# Audio_Amplifier.net
KiCad netlist of a schematic drawn in Altium Designer
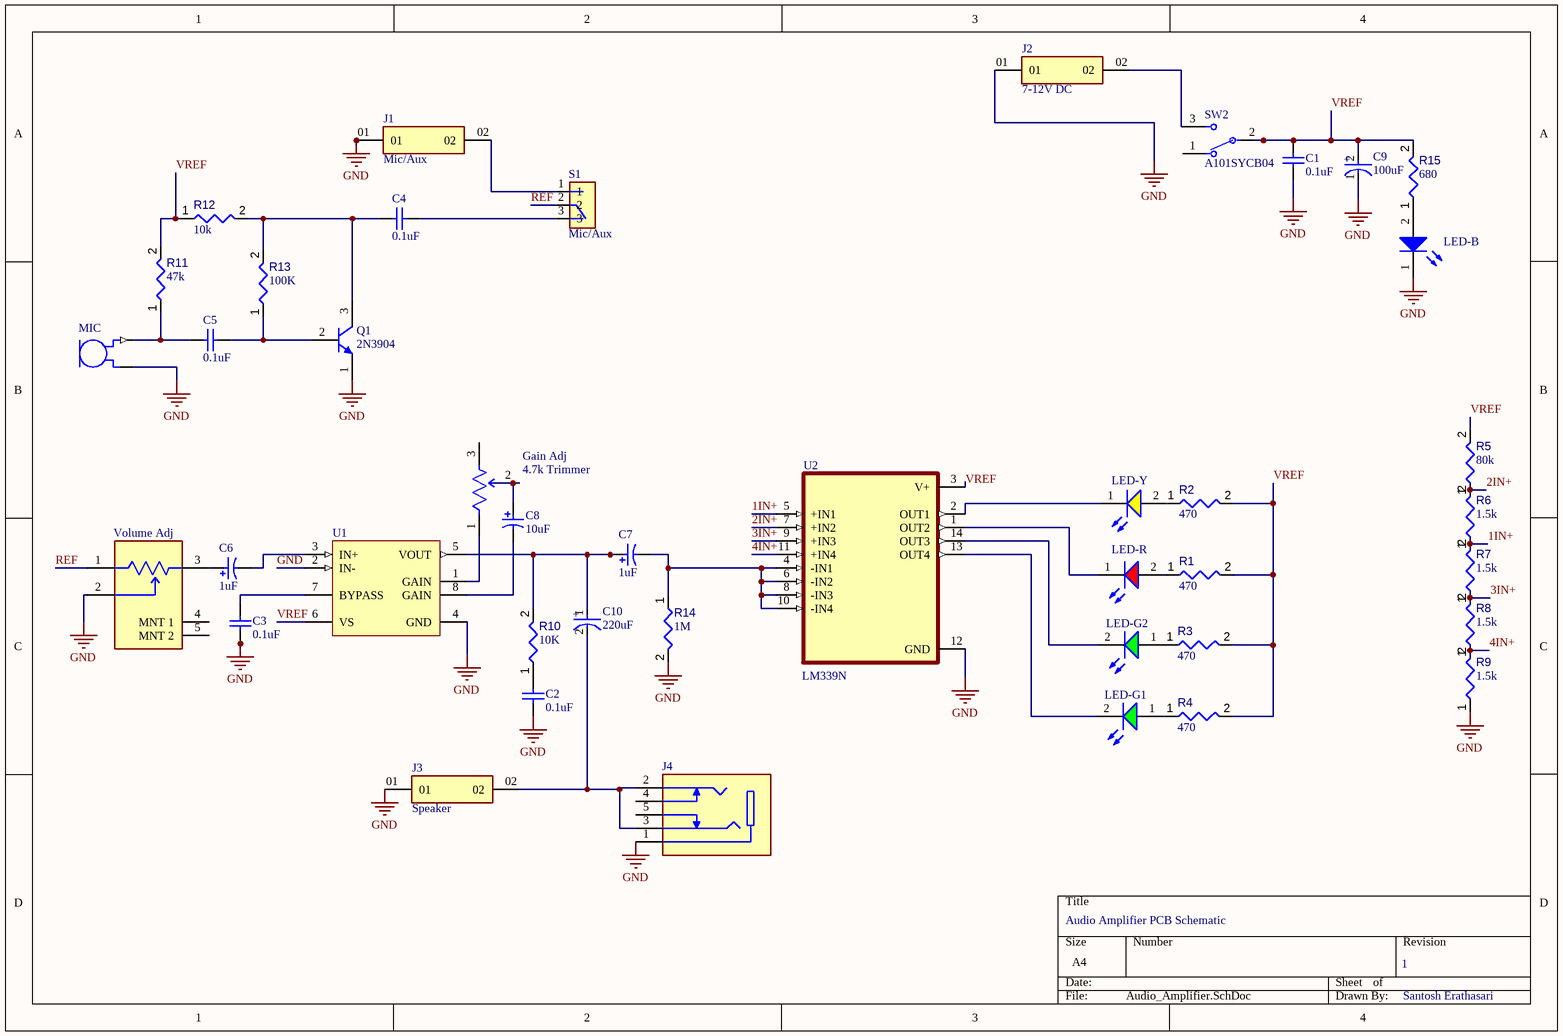
[diagram p0: Audio_Amplifier.SchDoc]

(export (version "E")
  (design (tool "Eeschema 10.0.6"))
  (components
    (comp (ref "C1")
      (value "0.1uF")
      (footprint "CAPR51-254-508X318X736")
      (libsource (lib "Altium Content Vault") (part "CAP-NP-2"))
    )
    (comp (ref "C2")
      (value "0.1uF")
      (footprint "CAPR51-254-508X318X736")
      (libsource (lib "Altium Content Vault") (part "CAP-NP-2"))
    )
    (comp (ref "C3")
      (value "0.1uF")
      (footprint "CAPR51-254-508X318X736")
      (libsource (lib "Altium Content Vault") (part "CAP-NP-2"))
    )
    (comp (ref "C4")
      (value "0.1uF")
      (footprint "CAPR51-254-508X318X736")
      (libsource (lib "Altium Content Vault") (part "CAP-NP-2"))
    )
    (comp (ref "C5")
      (value "0.1uF")
      (footprint "CAPR51-254-508X318X736")
      (libsource (lib "Altium Content Vault") (part "CAP-NP-2"))
    )
    (comp (ref "C6")
      (value "1uF")
      (footprint "CAPPR55-200-1100X500X1200")
      (description "Aluminum Electrolytic Capacitor, 1 uF, +/- 20%, 50 V, -55 to 105 degC, 2-Pin THD, RoHS, Bulk")
      (libsource (lib "Altium Content Vault") (part "CAP-P-2"))
    )
    (comp (ref "C7")
      (value "1uF")
      (footprint "CAPPR55-200-1100X500X1200")
      (description "Aluminum Electrolytic Capacitor, 1 uF, +/- 20%, 50 V, -55 to 105 degC, 2-Pin THD, RoHS, Bulk")
      (libsource (lib "Altium Content Vault") (part "CAP-P-2"))
    )
    (comp (ref "C8")
      (value "10uF")
      (footprint "CAPPR55-200-1100X500X1200")
      (description "Aluminum Electrolytic Capacitor, 10 uF, +/- 20%, 50 V, -40 to 85 degC, 2-Pin THD, RoHS, Bulk")
      (fields (field (name "MANUFACTURER") "Panasonic") (field (name "TOLERANCE") "20%"))
      (libsource (lib "Altium Content Vault") (part "CAP-P-2"))
    )
    (comp (ref "C9")
      (value "100uF")
      (footprint "FP-RAD-TH-D_6_3_0_5-L_11-MFG")
      (description "Aluminum Electrolytic Capacitors (Radial Lead Type) 100uF ±20% 25V")
      (libsource (lib "Altium Content Vault") (part "a00bbbee19879c290e62620ae7e47b1"))
    )
    (comp (ref "C10")
      (value "220uF")
      (footprint "FP-EEU-FC1V221L-MFG")
      (description "CAP ALUM 220UF 20% 35V RADIAL")
      (fields
        (field (name "OCTOPART") "https://octopart.com/eeu-fc1v221l-panasonic-39478519")
        (field (name "MANUFACTURER") "Panasonic Electronic Components")
      )
      (libsource (lib "Altium Content Vault") (part "385ce6c70a3ab0aa1e866f00bd8ed49"))
    )
    (comp (ref "Gain Adj")
      (value "4.7k Trimmer")
      (footprint "FP-3362U-MFG")
      (description "TRIMMER 200K OHM 0.5W PC PIN TOP")
      (fields (field (name "TOLERANCE") "10%"))
      (libsource (lib "Altium Content Vault") (part "2dcfd2547301a7d3209a5e99acfd772"))
    )
    (comp (ref "J1")
      (value "Mic/Aux")
      (footprint "SAMTEC_HTSW-101-08-T-D")
      (fields (field (name "MP") "HTSW-101-08-T-D"))
      (libsource (lib "HTSW-101-08-T-D") (part "HTSW-101-08-T-D"))
    )
    (comp (ref "J2")
      (value "7-12V DC")
      (footprint "SAMTEC_HTSW-101-08-T-D")
      (fields (field (name "MP") "HTSW-101-08-T-D"))
      (libsource (lib "HTSW-101-08-T-D") (part "HTSW-101-08-T-D"))
    )
    (comp (ref "J3")
      (value "Speaker")
      (footprint "SAMTEC_HTSW-101-08-T-D")
      (fields (field (name "MP") "HTSW-101-08-T-D"))
      (libsource (lib "HTSW-101-08-T-D") (part "HTSW-101-08-T-D"))
    )
    (comp (ref "J4")
      (value "SJ1-3525NG")
      (footprint "CUI_SJ1-3525NG")
      (description "3.5 mm Right-Angle Stereo Jack, 5 Pin PCB Mount, Isolated Ground")
      (libsource (lib "Santosh's Playhouse") (part "SJ1-3525NG"))
    )
    (comp (ref "LED-B")
      (value "LED-B")
      (footprint "WL-TMRW_D5.8H11.7")
      (libsource (lib "Altium Content Vault") (part "LED_Blue_2A-1K"))
    )
    (comp (ref "LED-G1")
      (value "151051VS04000")
      (footprint "WL-TMRC_D5.9H8.7")
      (libsource (lib "Altium Content Vault") (part "LED_Green_1A-2K"))
    )
    (comp (ref "LED-G2")
      (value "151051VS04000")
      (footprint "WL-TMRC_D5.9H8.7")
      (libsource (lib "Altium Content Vault") (part "LED_Green_1A-2K"))
    )
    (comp (ref "LED-R")
      (value "151053RS03000")
      (footprint "WL-TMRW_D5.8H11.7")
      (libsource (lib "Altium Content Vault") (part "LED_Red_2A-1K"))
    )
    (comp (ref "LED-Y")
      (value "LED-Y")
      (footprint "WL-TMRW_D5.8H11.7")
      (libsource (lib "Altium Content Vault") (part "LED_Yellow_2A-1K"))
    )
    (comp (ref "MIC")
      (value "CMA-6542PF")
      (footprint "CUI_CMA-6542PF")
      (description "9.7 mm, Omnidirectional, PCB Mount, 4.5 Vdc, Electret Condenser Microphone")
      (fields (field (name "MF") "CUI Devices"))
      (libsource (lib "Santosh's Playhouse") (part "CMA-6542PF"))
    )
    (comp (ref "Q1")
      (value "2N3904")
      (footprint "ONSC-TO-92-3-29-11")
      (description "General Purpose Transistor, NPN Silicon, 200 mA, 60 V, -55 to 150 degC, 3-Pin TO-92, RoHS, Bulk")
      (fields (field (name "MANUFACTURER") "ONSemiconductor"))
      (libsource (lib "Altium Content Vault") (part "BJT-NPN-EBC-3"))
    )
    (comp (ref "R1")
      (value "470")
      (footprint "RESA60-630X240")
      (description "Axial Resistor, 10 KOhm, +/- 1%, 0.25 W, -55 to 155 degC, 2-Pin THD, RoHS, Bulk")
      (fields (field (name "TOLERANCE") "1%") (field (name "POWER") "250mW"))
      (libsource (lib "Santosh's Playhouse") (part "RES-2"))
    )
    (comp (ref "R2")
      (value "470")
      (footprint "RESA60-630X240")
      (description "Axial Resistor, 10 KOhm, +/- 1%, 0.25 W, -55 to 155 degC, 2-Pin THD, RoHS, Bulk")
      (fields (field (name "TOLERANCE") "1%") (field (name "POWER") "250mW"))
      (libsource (lib "Santosh's Playhouse") (part "RES-2"))
    )
    (comp (ref "R3")
      (value "470")
      (footprint "RESA60-630X240")
      (description "Axial Resistor, 10 KOhm, +/- 1%, 0.25 W, -55 to 155 degC, 2-Pin THD, RoHS, Bulk")
      (fields (field (name "TOLERANCE") "1%") (field (name "POWER") "250mW"))
      (libsource (lib "Santosh's Playhouse") (part "RES-2"))
    )
    (comp (ref "R4")
      (value "470")
      (footprint "RESA60-630X240")
      (description "Axial Resistor, 10 KOhm, +/- 1%, 0.25 W, -55 to 155 degC, 2-Pin THD, RoHS, Bulk")
      (fields (field (name "TOLERANCE") "1%") (field (name "POWER") "250mW"))
      (libsource (lib "Santosh's Playhouse") (part "RES-2"))
    )
    (comp (ref "R5")
      (value "80k")
      (footprint "RESA60-630X240")
      (description "Axial Resistor, 10 KOhm, +/- 1%, 0.25 W, -55 to 155 degC, 2-Pin THD, RoHS, Bulk")
      (fields (field (name "TOLERANCE") "1%") (field (name "POWER") "250mW"))
      (libsource (lib "Santosh's Playhouse") (part "RES-2"))
    )
    (comp (ref "R6")
      (value "1.5k")
      (footprint "RESA60-630X240")
      (description "Axial Resistor, 10 KOhm, +/- 1%, 0.25 W, -55 to 155 degC, 2-Pin THD, RoHS, Bulk")
      (fields (field (name "TOLERANCE") "1%") (field (name "POWER") "250mW"))
      (libsource (lib "Santosh's Playhouse") (part "RES-2"))
    )
    (comp (ref "R7")
      (value "1.5k")
      (footprint "RESA60-630X240")
      (description "Axial Resistor, 10 KOhm, +/- 1%, 0.25 W, -55 to 155 degC, 2-Pin THD, RoHS, Bulk")
      (fields (field (name "TOLERANCE") "1%") (field (name "POWER") "250mW"))
      (libsource (lib "Santosh's Playhouse") (part "RES-2"))
    )
    (comp (ref "R8")
      (value "1.5k")
      (footprint "RESA60-630X240")
      (description "Axial Resistor, 10 KOhm, +/- 1%, 0.25 W, -55 to 155 degC, 2-Pin THD, RoHS, Bulk")
      (fields (field (name "TOLERANCE") "1%") (field (name "POWER") "250mW"))
      (libsource (lib "Santosh's Playhouse") (part "RES-2"))
    )
    (comp (ref "R9")
      (value "1.5k")
      (footprint "RESA60-630X240")
      (description "Axial Resistor, 10 KOhm, +/- 1%, 0.25 W, -55 to 155 degC, 2-Pin THD, RoHS, Bulk")
      (fields (field (name "TOLERANCE") "1%") (field (name "POWER") "250mW"))
      (libsource (lib "Santosh's Playhouse") (part "RES-2"))
    )
    (comp (ref "R10")
      (value "10K")
      (footprint "RESA60-630X240")
      (description "Axial Resistor, 10 KOhm, +/- 1%, 0.25 W, -55 to 155 degC, 2-Pin THD, RoHS, Bulk")
      (fields (field (name "TOLERANCE") "1%") (field (name "POWER") "250mW"))
      (libsource (lib "Santosh's Playhouse") (part "RES-2"))
    )
    (comp (ref "R11")
      (value "47k")
      (footprint "RESA60-630X240")
      (description "Axial Resistor, 10 KOhm, +/- 1%, 0.25 W, -55 to 155 degC, 2-Pin THD, RoHS, Bulk")
      (fields (field (name "TOLERANCE") "1%") (field (name "POWER") "250mW"))
      (libsource (lib "Santosh's Playhouse") (part "RES-2"))
    )
    (comp (ref "R12")
      (value "10k")
      (footprint "RESA60-630X240")
      (description "Axial Resistor, 10 KOhm, +/- 1%, 0.25 W, -55 to 155 degC, 2-Pin THD, RoHS, Bulk")
      (fields (field (name "TOLERANCE") "1%") (field (name "POWER") "250mW"))
      (libsource (lib "Santosh's Playhouse") (part "RES-2"))
    )
    (comp (ref "R13")
      (value "100K")
      (footprint "RESA60-630X240")
      (description "Axial Resistor, 10 KOhm, +/- 1%, 0.25 W, -55 to 155 degC, 2-Pin THD, RoHS, Bulk")
      (fields (field (name "TOLERANCE") "1%") (field (name "POWER") "250mW"))
      (libsource (lib "Santosh's Playhouse") (part "RES-2"))
    )
    (comp (ref "R14")
      (value "1M")
      (footprint "RESA60-630X240")
      (description "Axial Resistor, 10 KOhm, +/- 1%, 0.25 W, -55 to 155 degC, 2-Pin THD, RoHS, Bulk")
      (fields (field (name "TOLERANCE") "1%") (field (name "POWER") "250mW"))
      (libsource (lib "Santosh's Playhouse") (part "RES-2"))
    )
    (comp (ref "R15")
      (value "680")
      (footprint "RESA60-630X240")
      (description "Axial Resistor, 10 KOhm, +/- 1%, 0.25 W, -55 to 155 degC, 2-Pin THD, RoHS, Bulk")
      (fields (field (name "TOLERANCE") "1%") (field (name "POWER") "250mW"))
      (libsource (lib "Santosh's Playhouse") (part "RES-2"))
    )
    (comp (ref "S1")
      (value "Mic/Aux")
      (footprint "SW_OS102011MS2QN1")
      (description "SLIDE SWITCH SPDT T/H ON-ON BBM")
      (fields (field (name "MP") "OS102011MS2QN1") (field (name "DIGI-KEY_PART_NUMBER") "CKN9565-ND"))
      (libsource (lib "OS102011MS2QN1") (part "OS102011MS2QN1"))
    )
    (comp (ref "SW2")
      (value "A101SYCB04")
      (footprint "FP-A101SYCB04-MFG")
      (description "SWITCH TOGGLE SPDT 0.4VA 20V")
      (libsource (lib "Altium Content Vault") (part "52c419afdc2a387c7d548259a9aeefb"))
    )
    (comp (ref "U1")
      (value "LM386N-1")
      (footprint "P0008A")
      (description "Low Voltage Audio Power Amplifier, 8-pin MDIP, Pb-Free")
      (fields (field (name "MANUFACTURER") "Texas Instruments"))
      (libsource (lib "Altium Content Vault") (part "AMP-APA-LM386-8"))
    )
    (comp (ref "U2")
      (value "LM339N")
      (footprint "DIP794W45P254L1969H508Q14")
      (description "Low Power Low Offset Voltage Quad Comparator")
      (fields (field (name "MP") "LM339N/NOPB") (field (name "MF") "Texas Instruments"))
      (libsource (lib "LM339N_NOPB") (part "LM339N/NOPB"))
    )
    (comp (ref "Volume Adj")
      (value "PTV09A-8025U-B103")
      (footprint "FP-PTV09-8-MFG")
      (description "POT 10K OHM 1/20W CARBON LINEAR")
      (fields (field (name "TOLERANCE") "20%"))
      (libsource (lib "Altium Content Vault") (part "d61d280540b277cc0195e43a024dbb5"))
    )
  )
  (nets
    (net (code "1") (name "/1IN+") (class "Default")
      (node (ref "R6") (pin "1") (pinfunction "1_1") (pintype "passive"))
      (node (ref "R7") (pin "2") (pinfunction "2_2") (pintype "passive"))
      (node (ref "U2") (pin "5") (pinfunction "+IN1_5") (pintype "input"))
    )
    (net (code "2") (name "/2IN+") (class "Default")
      (node (ref "R5") (pin "1") (pinfunction "1_1") (pintype "passive"))
      (node (ref "R6") (pin "2") (pinfunction "2_2") (pintype "passive"))
      (node (ref "U2") (pin "7") (pinfunction "+IN2_7") (pintype "input"))
    )
    (net (code "3") (name "/3IN+") (class "Default")
      (node (ref "R7") (pin "1") (pinfunction "1_1") (pintype "passive"))
      (node (ref "R8") (pin "2") (pinfunction "2_2") (pintype "passive"))
      (node (ref "U2") (pin "9") (pinfunction "+IN3_9") (pintype "input"))
    )
    (net (code "4") (name "/4IN+") (class "Default")
      (node (ref "R8") (pin "1") (pinfunction "1_1") (pintype "passive"))
      (node (ref "R9") (pin "2") (pinfunction "2_2") (pintype "passive"))
      (node (ref "U2") (pin "11") (pinfunction "+IN4_11") (pintype "input"))
    )
    (net (code "5") (name "/REF") (class "Default")
      (node (ref "S1") (pin "2") (pinfunction "2_2") (pintype "passive"))
      (node (ref "Volume Adj") (pin "1") (pinfunction "1_1") (pintype "passive"))
    )
    (net (code "6") (name "/VREF") (class "Default")
      (node (ref "C1") (pin "1") (pinfunction "1_1") (pintype "passive"))
      (node (ref "C9") (pin "2") (pinfunction "A_2") (pintype "passive"))
      (node (ref "R1") (pin "2") (pinfunction "2_2") (pintype "passive"))
      (node (ref "R11") (pin "2") (pinfunction "2_2") (pintype "passive"))
      (node (ref "R12") (pin "1") (pinfunction "1_1") (pintype "passive"))
      (node (ref "R15") (pin "2") (pinfunction "2_2") (pintype "passive"))
      (node (ref "R2") (pin "2") (pinfunction "2_2") (pintype "passive"))
      (node (ref "R3") (pin "2") (pinfunction "2_2") (pintype "passive"))
      (node (ref "R4") (pin "2") (pinfunction "2_2") (pintype "passive"))
      (node (ref "R5") (pin "2") (pinfunction "2_2") (pintype "passive"))
      (node (ref "SW2") (pin "2") (pinfunction "2_2") (pintype "passive"))
      (node (ref "U1") (pin "6") (pinfunction "VS_6") (pintype "power_in"))
      (node (ref "U2") (pin "3") (pinfunction "V+_3") (pintype "power_in"))
    )
    (net (code "7") (name "GND") (class "Default")
      (node (ref "C1") (pin "2") (pinfunction "2_2") (pintype "passive"))
      (node (ref "C2") (pin "1") (pinfunction "1_1") (pintype "passive"))
      (node (ref "C3") (pin "1") (pinfunction "1_1") (pintype "passive"))
      (node (ref "C9") (pin "1") (pinfunction "C_1") (pintype "passive"))
      (node (ref "J1") (pin "01") (pinfunction "01_01") (pintype "passive"))
      (node (ref "J2") (pin "01") (pinfunction "01_01") (pintype "passive"))
      (node (ref "J3") (pin "01") (pinfunction "01_01") (pintype "passive"))
      (node (ref "J4") (pin "1") (pinfunction "1_1") (pintype "passive"))
      (node (ref "LED-B") (pin "1") (pinfunction "K_1") (pintype "passive"))
      (node (ref "MIC") (pin "GND") (pinfunction "GND_GND") (pintype "power_in"))
      (node (ref "Q1") (pin "1") (pinfunction "E_1") (pintype "passive"))
      (node (ref "R14") (pin "2") (pinfunction "2_2") (pintype "passive"))
      (node (ref "R9") (pin "1") (pinfunction "1_1") (pintype "passive"))
      (node (ref "U1") (pin "2") (pinfunction "IN-_2") (pintype "input"))
      (node (ref "U1") (pin "4") (pinfunction "GND_4") (pintype "power_in"))
      (node (ref "U2") (pin "12") (pinfunction "GND_12") (pintype "power_in"))
      (node (ref "Volume Adj") (pin "2") (pinfunction "2_2") (pintype "passive"))
    )
    (net (code "8") (name "Net-(C2-Pad2)") (class "Default")
      (node (ref "C2") (pin "2") (pinfunction "2_2") (pintype "passive"))
      (node (ref "R10") (pin "1") (pinfunction "1_1") (pintype "passive"))
    )
    (net (code "9") (name "Net-(C4-Pad2)") (class "Default")
      (node (ref "C4") (pin "2") (pinfunction "2_2") (pintype "passive"))
      (node (ref "S1") (pin "3") (pinfunction "3_3") (pintype "passive"))
    )
    (net (code "10") (name "Net-(C5-Pad1)") (class "Default")
      (node (ref "C5") (pin "1") (pinfunction "1_1") (pintype "passive"))
      (node (ref "MIC") (pin "OUT") (pinfunction "OUT_OUT") (pintype "output"))
      (node (ref "R11") (pin "1") (pinfunction "1_1") (pintype "passive"))
    )
    (net (code "11") (name "Net-(C6-Pad1)") (class "Default")
      (node (ref "C6") (pin "1") (pinfunction "1_1") (pintype "passive"))
      (node (ref "Volume Adj") (pin "3") (pinfunction "3_3") (pintype "passive"))
    )
    (net (code "12") (name "Net-(C8-Pad2)") (class "Default")
      (node (ref "C8") (pin "2") (pinfunction "2_2") (pintype "passive"))
      (node (ref "U1") (pin "8") (pinfunction "GAIN_8") (pintype "passive"))
    )
    (net (code "13") (name "Net-(C10-A)") (class "Default")
      (node (ref "C10") (pin "2") (pinfunction "A_2") (pintype "passive"))
      (node (ref "J3") (pin "02") (pinfunction "02_02") (pintype "passive"))
      (node (ref "J4") (pin "2") (pinfunction "2_2") (pintype "passive"))
      (node (ref "J4") (pin "3") (pinfunction "3_3") (pintype "passive"))
    )
    (net (code "14") (name "Net-(C10-C)") (class "Default")
      (node (ref "C10") (pin "1") (pinfunction "C_1") (pintype "passive"))
      (node (ref "C7") (pin "1") (pinfunction "1_1") (pintype "passive"))
      (node (ref "R10") (pin "2") (pinfunction "2_2") (pintype "passive"))
      (node (ref "U1") (pin "5") (pinfunction "VOUT_5") (pintype "output"))
    )
    (net (code "15") (name "Net-(Gain Adj-CCW)") (class "Default")
      (node (ref "Gain Adj") (pin "1") (pinfunction "CCW_1") (pintype "passive"))
      (node (ref "U1") (pin "1") (pinfunction "GAIN_1") (pintype "passive"))
    )
    (net (code "16") (name "Net-(Gain Adj-WIPER)") (class "Default")
      (node (ref "C8") (pin "1") (pinfunction "1_1") (pintype "passive"))
      (node (ref "Gain Adj") (pin "2") (pinfunction "WIPER_2") (pintype "passive"))
    )
    (net (code "17") (name "Net-(J1-Pad02)") (class "Default")
      (node (ref "J1") (pin "02") (pinfunction "02_02") (pintype "passive"))
      (node (ref "S1") (pin "1") (pinfunction "1_1") (pintype "passive"))
    )
    (net (code "18") (name "Net-(J2-Pad02)") (class "Default")
      (node (ref "J2") (pin "02") (pinfunction "02_02") (pintype "passive"))
      (node (ref "SW2") (pin "3") (pinfunction "3_3") (pintype "passive"))
    )
    (net (code "19") (name "Net-(LED-B-A)") (class "Default")
      (node (ref "LED-B") (pin "2") (pinfunction "A_2") (pintype "passive"))
      (node (ref "R15") (pin "1") (pinfunction "1_1") (pintype "passive"))
    )
    (net (code "20") (name "Net-(LED-G1-A)") (class "Default")
      (node (ref "LED-G1") (pin "1") (pinfunction "A_1") (pintype "passive"))
      (node (ref "R4") (pin "1") (pinfunction "1_1") (pintype "passive"))
    )
    (net (code "21") (name "Net-(LED-G1-K)") (class "Default")
      (node (ref "LED-G1") (pin "2") (pinfunction "K_2") (pintype "passive"))
      (node (ref "U2") (pin "13") (pinfunction "OUT4_13") (pintype "output"))
    )
    (net (code "22") (name "Net-(LED-G2-A)") (class "Default")
      (node (ref "LED-G2") (pin "1") (pinfunction "A_1") (pintype "passive"))
      (node (ref "R3") (pin "1") (pinfunction "1_1") (pintype "passive"))
    )
    (net (code "23") (name "Net-(LED-G2-K)") (class "Default")
      (node (ref "LED-G2") (pin "2") (pinfunction "K_2") (pintype "passive"))
      (node (ref "U2") (pin "14") (pinfunction "OUT3_14") (pintype "output"))
    )
    (net (code "24") (name "Net-(LED-R-A)") (class "Default")
      (node (ref "LED-R") (pin "2") (pinfunction "A_2") (pintype "passive"))
      (node (ref "R1") (pin "1") (pinfunction "1_1") (pintype "passive"))
    )
    (net (code "25") (name "Net-(LED-R-K)") (class "Default")
      (node (ref "LED-R") (pin "1") (pinfunction "K_1") (pintype "passive"))
      (node (ref "U2") (pin "1") (pinfunction "OUT2_1") (pintype "output"))
    )
    (net (code "26") (name "Net-(LED-Y-A)") (class "Default")
      (node (ref "LED-Y") (pin "2") (pinfunction "A_2") (pintype "passive"))
      (node (ref "R2") (pin "1") (pinfunction "1_1") (pintype "passive"))
    )
    (net (code "27") (name "Net-(LED-Y-K)") (class "Default")
      (node (ref "LED-Y") (pin "1") (pinfunction "K_1") (pintype "passive"))
      (node (ref "U2") (pin "2") (pinfunction "OUT1_2") (pintype "output"))
    )
    (net (code "28") (name "Net-(Q1-B)") (class "Default")
      (node (ref "C5") (pin "2") (pinfunction "2_2") (pintype "passive"))
      (node (ref "Q1") (pin "2") (pinfunction "B_2") (pintype "passive"))
      (node (ref "R13") (pin "1") (pinfunction "1_1") (pintype "passive"))
    )
    (net (code "29") (name "Net-(Q1-C)") (class "Default")
      (node (ref "C4") (pin "1") (pinfunction "1_1") (pintype "passive"))
      (node (ref "Q1") (pin "3") (pinfunction "C_3") (pintype "passive"))
      (node (ref "R12") (pin "2") (pinfunction "2_2") (pintype "passive"))
      (node (ref "R13") (pin "2") (pinfunction "2_2") (pintype "passive"))
    )
    (net (code "30") (name "Net-(U1-BYPASS)") (class "Default")
      (node (ref "C3") (pin "2") (pinfunction "2_2") (pintype "passive"))
      (node (ref "U1") (pin "7") (pinfunction "BYPASS_7") (pintype "passive"))
    )
    (net (code "31") (name "Net-(U1-IN+)") (class "Default")
      (node (ref "C6") (pin "2") (pinfunction "2_2") (pintype "passive"))
      (node (ref "U1") (pin "3") (pinfunction "IN+_3") (pintype "input"))
    )
    (net (code "32") (name "Net-(U2--IN1)") (class "Default")
      (node (ref "C7") (pin "2") (pinfunction "2_2") (pintype "passive"))
      (node (ref "R14") (pin "1") (pinfunction "1_1") (pintype "passive"))
      (node (ref "U2") (pin "10") (pinfunction "-IN4_10") (pintype "input"))
      (node (ref "U2") (pin "4") (pinfunction "-IN1_4") (pintype "input"))
      (node (ref "U2") (pin "6") (pinfunction "-IN2_6") (pintype "input"))
      (node (ref "U2") (pin "8") (pinfunction "-IN3_8") (pintype "input"))
    )
    (net (code "33") (name "unconnected-(Gain Adj-CW-Pad3)") (class "Default")
      (node (ref "Gain Adj") (pin "3") (pinfunction "CW_3") (pintype "passive"))
    )
    (net (code "34") (name "unconnected-(J4-Pad4)") (class "Default")
      (node (ref "J4") (pin "4") (pinfunction "4_4") (pintype "passive"))
    )
    (net (code "35") (name "unconnected-(J4-Pad5)") (class "Default")
      (node (ref "J4") (pin "5") (pinfunction "5_5") (pintype "passive"))
    )
    (net (code "36") (name "unconnected-(SW2-Pad1)") (class "Default")
      (node (ref "SW2") (pin "1") (pinfunction "1_1") (pintype "passive"))
    )
    (net (code "37") (name "unconnected-(Volume Adj-MNT_1-Pad4)") (class "Default")
      (node (ref "Volume Adj") (pin "4") (pinfunction "MNT_1_4") (pintype "passive"))
    )
    (net (code "38") (name "unconnected-(Volume Adj-MNT_2-Pad5)") (class "Default")
      (node (ref "Volume Adj") (pin "5") (pinfunction "MNT_2_5") (pintype "passive"))
    )
  )
)
